# SCH_BlackRacer.net
KiCad netlist of a schematic drawn in EasyEDA
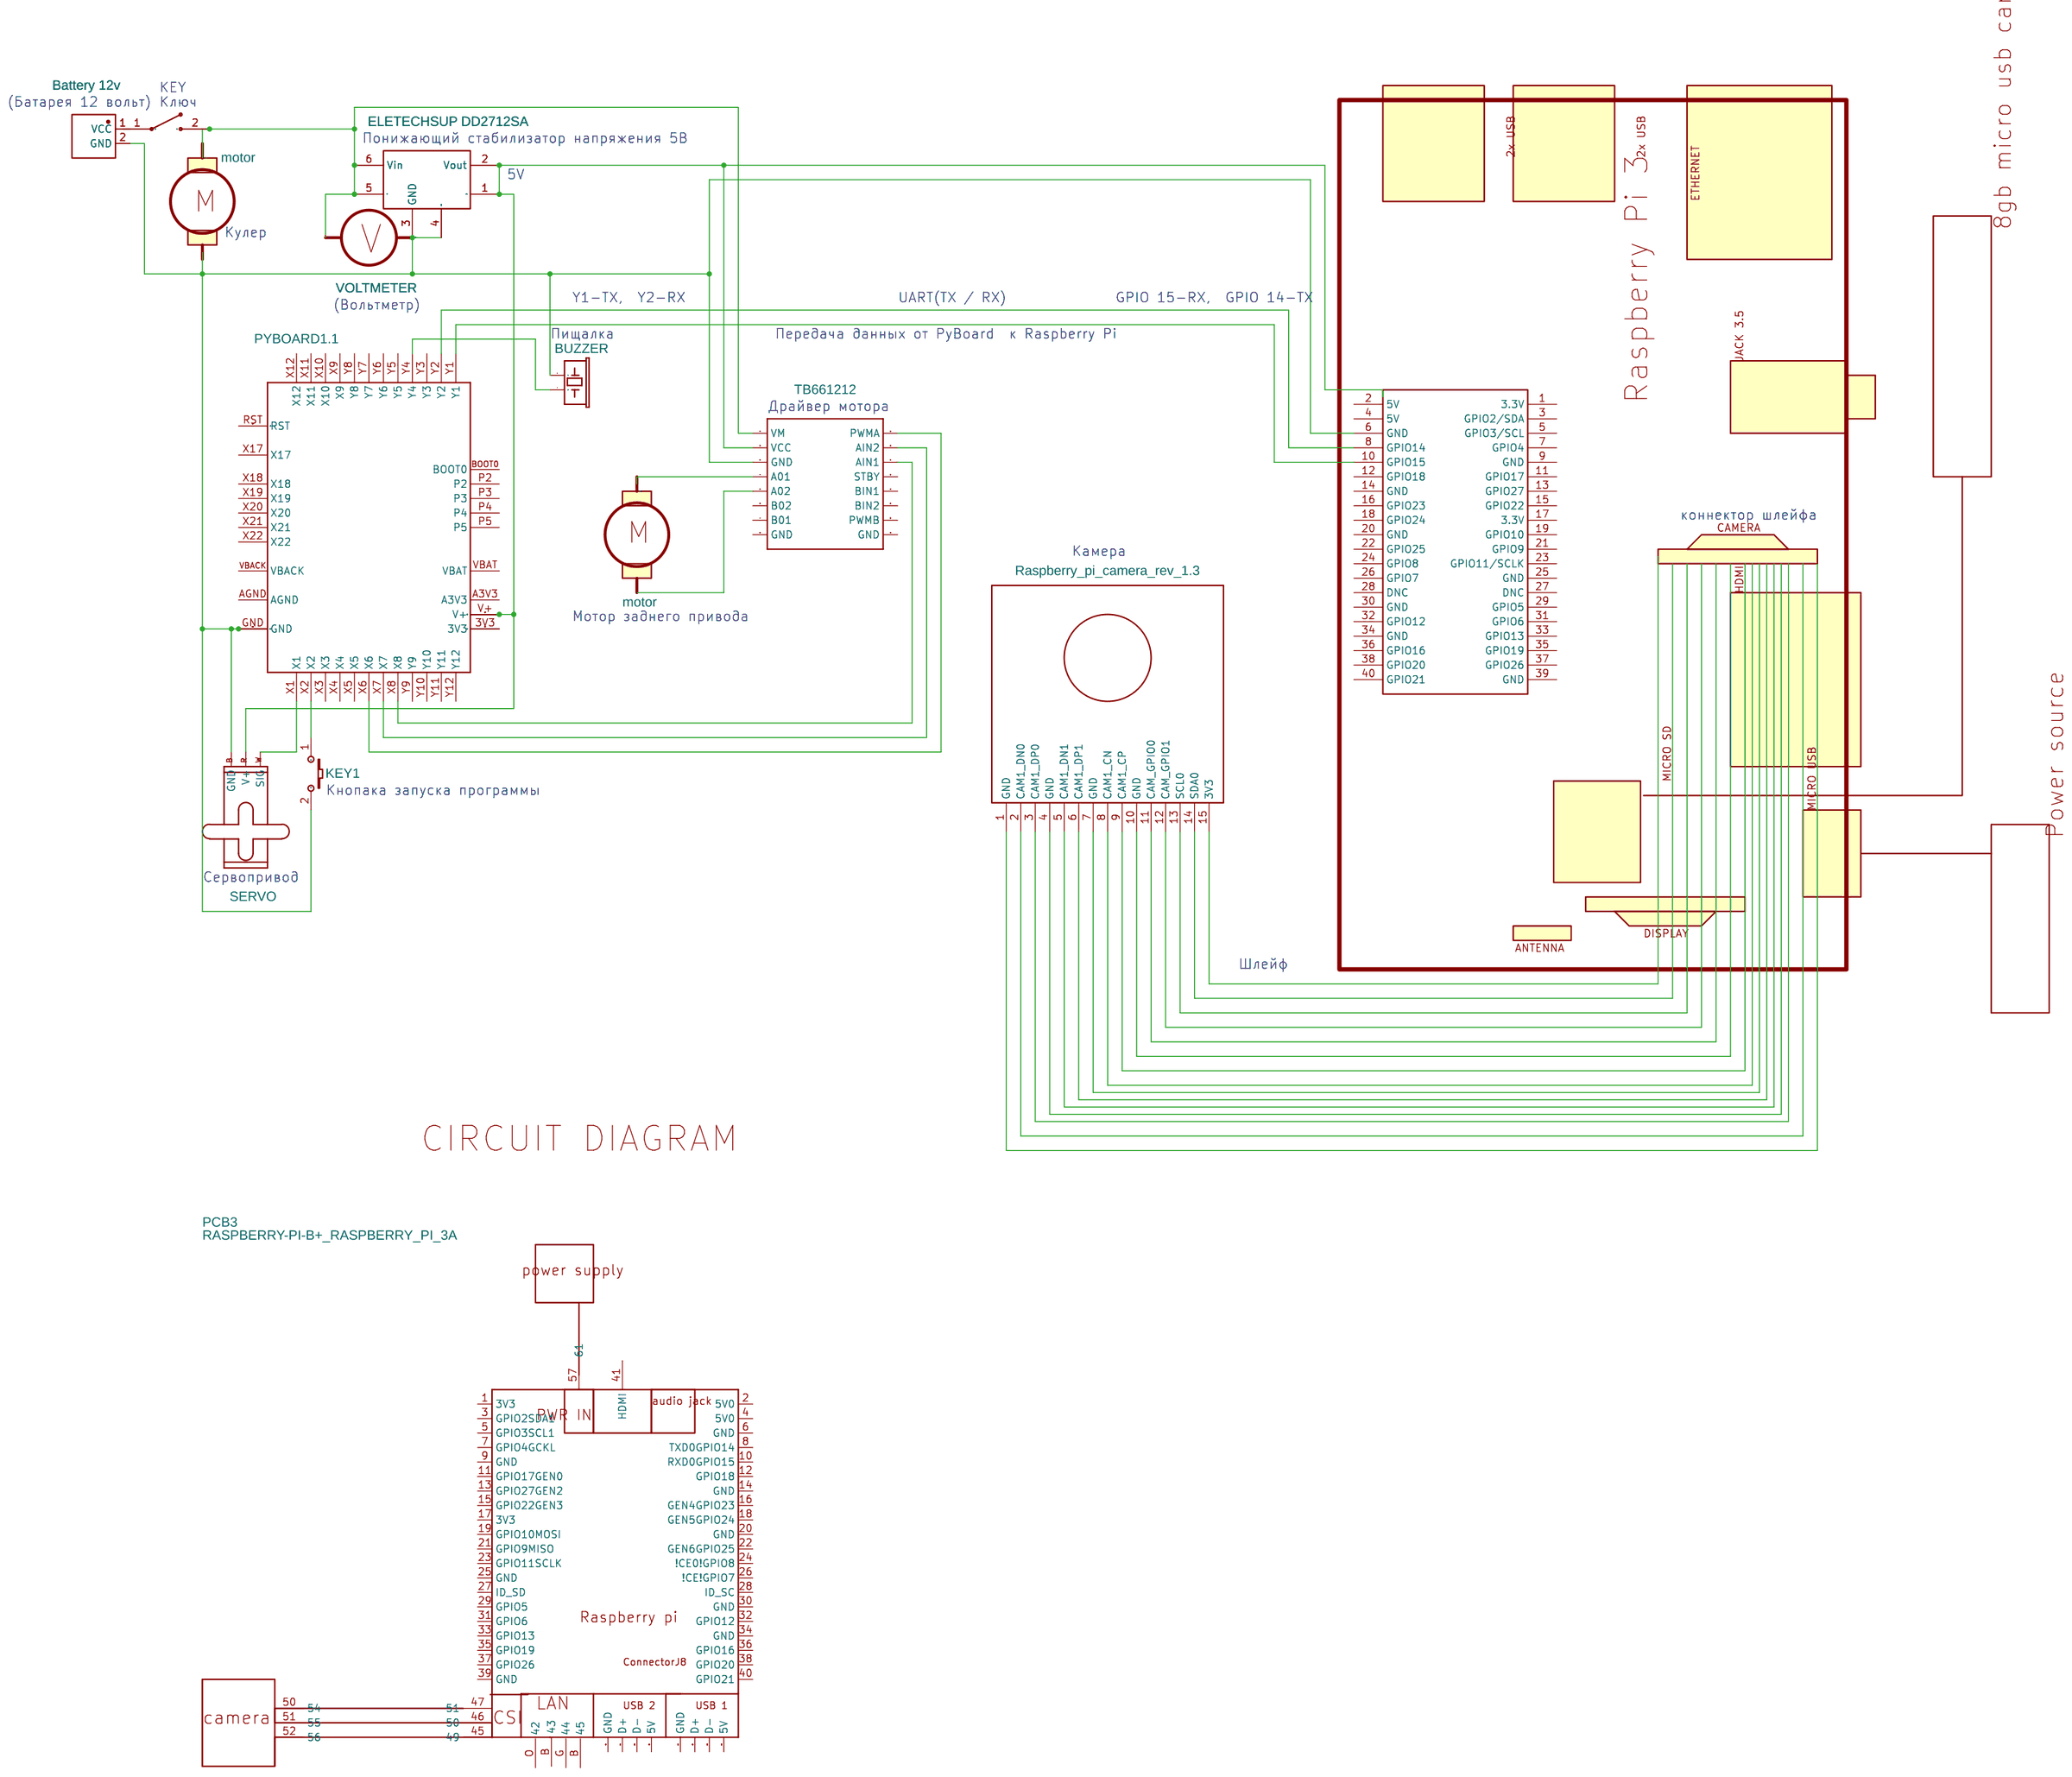
[diagram p0: schematic sheet]

(export (version "E")
  (design (tool "Eeschema 10.0.6"))
  (components
    (comp (ref "1") (value "PYBOARD1.1") (libsource (lib "") (part "PYBOARD1.1")))
    (comp (ref "KEY1")
      (value "K2-3.6×6.1_SMD")
      (fields
        (field (name "BOM_Manufacturer Part") "K2-1107ST-A4SW-06")
        (field (name "BOM_Supplier Part") "C118141")
      )
      (libsource (lib "") (part "K2-3.6×6.1_SMD"))
    )
    (comp (ref "M1") (value "SERVO") (libsource (lib "") (part "SERVO")))
    (comp (ref "M2") (value "motor") (libsource (lib "") (part "motor_1")))
    (comp (ref "M4") (value "motor") (libsource (lib "") (part "motor")))
    (comp (ref "P1") (value "VOLTMETER") (libsource (lib "") (part "VOLTMETER_XL")))
    (comp (ref "PCB3")
      (value "RASPBERRY-PI-B+_RASPBERRY_PI_3A")
      (libsource (lib "") (part "RASPBERRY-PI-B+_RASPBERRY_PI_3A"))
    )
    (comp (ref "SG1") (value "BUZZER") (libsource (lib "") (part "BUZZER")))
    (comp (ref "U1") (value "ELETECHSUP DD2712SA") (libsource (lib "") (part "DD2712SA")))
    (comp (ref "U2")
      (value "Raspberry Pi")
      (fields
        (field (name "BOM_Manufacturer Part") "RASPBERRY PI 3 Model B")
        (field (name "BOM_Supplier Part") "Raspberry Pi 3-B")
      )
      (libsource (lib "") (part "Raspberry Pi"))
    )
    (comp (ref "U4") (value "Battery 12v") (libsource (lib "") (part "Battery")))
    (comp (ref "U5")
      (value "Raspberry_pi_camera_rev_1.3")
      (libsource (lib "") (part "Raspberry_pi_camera_rev_1.3"))
    )
    (comp (ref "U7")
      (value "Botton")
      (fields (field (name "BOM_Manufacturer Part") "2A080") (field (name "BOM_Supplier Part") "12131"))
      (libsource (lib "") (part "Botton"))
    )
    (comp (ref "U9") (value "TB661212") (libsource (lib "") (part "TB661212")))
  )
  (nets
    (net (code "1") (name "Net-(1-3V3-Pad3V3-1)") (class "Default")
      (node (ref "1") (pin "3V3") (pinfunction "3V3_3V3") (pintype "bidirectional"))
      (node (ref "1") (pin "3V3-1") (pinfunction "3V3_3V3-1") (pintype "bidirectional"))
    )
    (net (code "2") (name "Net-(1-PadRST)") (class "Default")
      (node (ref "1") (pin "RST") (pinfunction "RST_RST") (pintype "bidirectional"))
      (node (ref "1") (pin "RST1") (pinfunction "RST_RST1") (pintype "bidirectional"))
    )
    (net (code "3") (name "Net-(1-PadX2)") (class "Default")
      (node (ref "1") (pin "X2") (pinfunction "X2_X2") (pintype "bidirectional"))
      (node (ref "KEY1") (pin "1") (pinfunction "1_1") (pintype "unspecified"))
    )
    (net (code "4") (name "Net-(M1-GND)") (class "Default")
      (node (ref "1") (pin "GND") (pinfunction "GND_GND") (pintype "bidirectional"))
      (node (ref "1") (pin "GND0") (pinfunction "GND_GND0") (pintype "bidirectional"))
      (node (ref "1") (pin "GND1") (pinfunction "GND_GND1") (pintype "bidirectional"))
      (node (ref "1") (pin "GND2") (pinfunction "GND_GND2") (pintype "bidirectional"))
      (node (ref "1") (pin "GND3") (pinfunction "GND_GND3") (pintype "bidirectional"))
      (node (ref "1") (pin "GND4") (pinfunction "GND_GND4") (pintype "bidirectional"))
      (node (ref "1") (pin "GND5") (pinfunction "GND_GND5") (pintype "bidirectional"))
      (node (ref "1") (pin "GND6") (pinfunction "GND_GND6") (pintype "bidirectional"))
      (node (ref "KEY1") (pin "2") (pinfunction "2_2") (pintype "unspecified"))
      (node (ref "M1") (pin "3") (pinfunction "GND_3") (pintype "bidirectional"))
      (node (ref "P1") (pin "2") (pinfunction "B_2") (pintype "unspecified"))
      (node (ref "SG1") (pin "+") (pinfunction "1_+") (pintype "unspecified"))
      (node (ref "U1") (pin "3") (pinfunction "GND_3") (pintype "unspecified"))
      (node (ref "U1") (pin "4") (pinfunction "GND_4") (pintype "unspecified"))
      (node (ref "U2") (pin "6") (pinfunction "GND_6") (pintype "unspecified"))
      (node (ref "U4") (pin "2") (pinfunction "GND_2") (pintype "unspecified"))
      (node (ref "U9") (pin "GND") (pinfunction "GND_GND") (pintype "passive"))
    )
    (net (code "5") (name "Net-(M1-SIG)") (class "Default")
      (node (ref "1") (pin "X1") (pinfunction "X1_X1") (pintype "bidirectional"))
      (node (ref "M1") (pin "1") (pinfunction "SIG_1") (pintype "bidirectional"))
    )
    (net (code "6") (name "Net-(M1-V+)") (class "Default")
      (node (ref "1") (pin "V+") (pinfunction "V+_V+") (pintype "bidirectional"))
      (node (ref "1") (pin "V+1") (pinfunction "V+_V+1") (pintype "bidirectional"))
      (node (ref "1") (pin "V+2") (pinfunction "V+_V+2") (pintype "bidirectional"))
      (node (ref "1") (pin "V+3") (pinfunction "V+_V+3") (pintype "bidirectional"))
      (node (ref "1") (pin "V+4") (pinfunction "V+_V+4") (pintype "bidirectional"))
      (node (ref "1") (pin "V+5") (pinfunction "V+_V+5") (pintype "bidirectional"))
      (node (ref "1") (pin "V+6") (pinfunction "V+_V+6") (pintype "bidirectional"))
      (node (ref "M1") (pin "2") (pinfunction "V+_2") (pintype "bidirectional"))
      (node (ref "U1") (pin "1") (pinfunction "Vout_1") (pintype "unspecified"))
      (node (ref "U1") (pin "2") (pinfunction "Vout_2") (pintype "unspecified"))
      (node (ref "U9") (pin "VCC") (pinfunction "VCC_VCC") (pintype "passive"))
    )
    (net (code "7") (name "Net-(P1-A)") (class "Default")
      (node (ref "M2") (pin "2") (pinfunction "2_2") (pintype "unspecified"))
      (node (ref "P1") (pin "1") (pinfunction "A_1") (pintype "unspecified"))
      (node (ref "U1") (pin "5") (pinfunction "Vin_5") (pintype "unspecified"))
      (node (ref "U1") (pin "6") (pinfunction "Vin_6") (pintype "unspecified"))
      (node (ref "U7") (pin "2") (pinfunction "1_2") (pintype "unspecified"))
      (node (ref "U9") (pin "VM") (pinfunction "VM_VM") (pintype "passive"))
    )
    (net (code "8") (name "Net-(SG1-2)") (class "Default")
      (node (ref "1") (pin "Y4") (pinfunction "Y4_Y4") (pintype "bidirectional"))
      (node (ref "SG1") (pin "-") (pinfunction "2_-") (pintype "unspecified"))
    )
    (net (code "9") (name "Net-(U2-GPIO14)") (class "Default")
      (node (ref "1") (pin "Y2") (pinfunction "Y2_Y2") (pintype "bidirectional"))
      (node (ref "U2") (pin "8") (pinfunction "GPIO14_8") (pintype "bidirectional"))
    )
    (net (code "10") (name "Net-(U2-GPIO15)") (class "Default")
      (node (ref "1") (pin "Y1") (pinfunction "Y1_Y1") (pintype "bidirectional"))
      (node (ref "U2") (pin "10") (pinfunction "GPIO15_10") (pintype "bidirectional"))
    )
    (net (code "11") (name "Net-(U9-AIN1)") (class "Default")
      (node (ref "1") (pin "X8") (pinfunction "X8_X8") (pintype "bidirectional"))
      (node (ref "U9") (pin "14") (pinfunction "AIN1_14") (pintype "unspecified"))
    )
    (net (code "12") (name "Net-(U9-AIN2)") (class "Default")
      (node (ref "1") (pin "X7") (pinfunction "X7_X7") (pintype "bidirectional"))
      (node (ref "U9") (pin "15") (pinfunction "AIN2_15") (pintype "unspecified"))
    )
    (net (code "13") (name "Net-(U9-PWMA)") (class "Default")
      (node (ref "1") (pin "X6") (pinfunction "X6_X6") (pintype "bidirectional"))
      (node (ref "U9") (pin "16") (pinfunction "PWMA_16") (pintype "unspecified"))
    )
    (net (code "14") (name "unconnected-(1-PadA3V3)") (class "Default")
      (node (ref "1") (pin "A3V3") (pinfunction "A3V3_A3V3") (pintype "bidirectional"))
    )
    (net (code "15") (name "unconnected-(1-PadAGND)") (class "Default")
      (node (ref "1") (pin "AGND") (pinfunction "AGND_AGND") (pintype "bidirectional"))
    )
    (net (code "16") (name "unconnected-(1-PadBOOT0)") (class "Default")
      (node (ref "1") (pin "BOOT0") (pinfunction "BOOT0_BOOT0") (pintype "bidirectional"))
    )
    (net (code "17") (name "unconnected-(1-PadP2)") (class "Default")
      (node (ref "1") (pin "P2") (pinfunction "P2_P2") (pintype "bidirectional"))
    )
    (net (code "18") (name "unconnected-(1-PadP3)") (class "Default")
      (node (ref "1") (pin "P3") (pinfunction "P3_P3") (pintype "bidirectional"))
    )
    (net (code "19") (name "unconnected-(1-PadP4)") (class "Default")
      (node (ref "1") (pin "P4") (pinfunction "P4_P4") (pintype "bidirectional"))
    )
    (net (code "20") (name "unconnected-(1-PadP5)") (class "Default")
      (node (ref "1") (pin "P5") (pinfunction "P5_P5") (pintype "bidirectional"))
    )
    (net (code "21") (name "unconnected-(1-PadVBACK)") (class "Default")
      (node (ref "1") (pin "VBACK") (pinfunction "VBACK_VBACK") (pintype "bidirectional"))
    )
    (net (code "22") (name "unconnected-(1-PadVBAT)") (class "Default")
      (node (ref "1") (pin "VBAT") (pinfunction "VBAT_VBAT") (pintype "bidirectional"))
    )
    (net (code "23") (name "unconnected-(1-PadX3)") (class "Default")
      (node (ref "1") (pin "X3") (pinfunction "X3_X3") (pintype "bidirectional"))
    )
    (net (code "24") (name "unconnected-(1-PadX4)") (class "Default")
      (node (ref "1") (pin "X4") (pinfunction "X4_X4") (pintype "bidirectional"))
    )
    (net (code "25") (name "unconnected-(1-PadX5)") (class "Default")
      (node (ref "1") (pin "X5") (pinfunction "X5_X5") (pintype "bidirectional"))
    )
    (net (code "26") (name "unconnected-(1-PadX9)") (class "Default")
      (node (ref "1") (pin "X9") (pinfunction "X9_X9") (pintype "bidirectional"))
    )
    (net (code "27") (name "unconnected-(1-PadX10)") (class "Default")
      (node (ref "1") (pin "X10") (pinfunction "X10_X10") (pintype "bidirectional"))
    )
    (net (code "28") (name "unconnected-(1-PadX11)") (class "Default")
      (node (ref "1") (pin "X11") (pinfunction "X11_X11") (pintype "bidirectional"))
    )
    (net (code "29") (name "unconnected-(1-PadX12)") (class "Default")
      (node (ref "1") (pin "X12") (pinfunction "X12_X12") (pintype "bidirectional"))
    )
    (net (code "30") (name "unconnected-(1-PadX17)") (class "Default")
      (node (ref "1") (pin "X17") (pinfunction "X17_X17") (pintype "bidirectional"))
    )
    (net (code "31") (name "unconnected-(1-PadX18)") (class "Default")
      (node (ref "1") (pin "X18") (pinfunction "X18_X18") (pintype "bidirectional"))
    )
    (net (code "32") (name "unconnected-(1-PadX19)") (class "Default")
      (node (ref "1") (pin "X19") (pinfunction "X19_X19") (pintype "bidirectional"))
    )
    (net (code "33") (name "unconnected-(1-PadX20)") (class "Default")
      (node (ref "1") (pin "X20") (pinfunction "X20_X20") (pintype "bidirectional"))
    )
    (net (code "34") (name "unconnected-(1-PadX21)") (class "Default")
      (node (ref "1") (pin "X21") (pinfunction "X21_X21") (pintype "bidirectional"))
    )
    (net (code "35") (name "unconnected-(1-PadX22)") (class "Default")
      (node (ref "1") (pin "X22") (pinfunction "X22_X22") (pintype "bidirectional"))
    )
    (net (code "36") (name "unconnected-(1-PadY3)") (class "Default")
      (node (ref "1") (pin "Y3") (pinfunction "Y3_Y3") (pintype "bidirectional"))
    )
    (net (code "37") (name "unconnected-(1-PadY5)") (class "Default")
      (node (ref "1") (pin "Y5") (pinfunction "Y5_Y5") (pintype "bidirectional"))
    )
    (net (code "38") (name "unconnected-(1-PadY6)") (class "Default")
      (node (ref "1") (pin "Y6") (pinfunction "Y6_Y6") (pintype "bidirectional"))
    )
    (net (code "39") (name "unconnected-(1-PadY7)") (class "Default")
      (node (ref "1") (pin "Y7") (pinfunction "Y7_Y7") (pintype "bidirectional"))
    )
    (net (code "40") (name "unconnected-(1-PadY8)") (class "Default")
      (node (ref "1") (pin "Y8") (pinfunction "Y8_Y8") (pintype "bidirectional"))
    )
    (net (code "41") (name "unconnected-(1-PadY9)") (class "Default")
      (node (ref "1") (pin "Y9") (pinfunction "Y9_Y9") (pintype "bidirectional"))
    )
    (net (code "42") (name "unconnected-(1-PadY10)") (class "Default")
      (node (ref "1") (pin "Y10") (pinfunction "Y10_Y10") (pintype "bidirectional"))
    )
    (net (code "43") (name "unconnected-(1-PadY11)") (class "Default")
      (node (ref "1") (pin "Y11") (pinfunction "Y11_Y11") (pintype "bidirectional"))
    )
    (net (code "44") (name "unconnected-(1-PadY12)") (class "Default")
      (node (ref "1") (pin "Y12") (pinfunction "Y12_Y12") (pintype "bidirectional"))
    )
    (net (code "45") (name "unconnected-(M4-Pad2)") (class "Default")
      (node (ref "M4") (pin "2") (pinfunction "2_2") (pintype "unspecified"))
    )
    (net (code "46") (name "unconnected-(PCB3-!CE!GPIO7-Pad26)") (class "Default")
      (node (ref "PCB3") (pin "26") (pinfunction "!CE!GPIO7_26") (pintype "unspecified"))
    )
    (net (code "47") (name "unconnected-(PCB3-!CE0!GPIO8-Pad24)") (class "Default")
      (node (ref "PCB3") (pin "24") (pinfunction "!CE0!GPIO8_24") (pintype "unspecified"))
    )
    (net (code "48") (name "unconnected-(PCB3-3V3-Pad1)") (class "Default")
      (node (ref "PCB3") (pin "1") (pinfunction "3V3_1") (pintype "unspecified"))
    )
    (net (code "49") (name "unconnected-(PCB3-3V3-Pad17)") (class "Default")
      (node (ref "PCB3") (pin "17") (pinfunction "3V3_17") (pintype "unspecified"))
    )
    (net (code "50") (name "unconnected-(PCB3-5V-PadPE_BR)") (class "Default")
      (node (ref "PCB3") (pin "PE_BR") (pinfunction "5V_PE_BR") (pintype "unspecified"))
    )
    (net (code "51") (name "unconnected-(PCB3-5V-PadPE_BR)_1") (class "Default")
      (node (ref "PCB3") (pin "PE_BR") (pinfunction "5V_PE_BR") (pintype "unspecified"))
    )
    (net (code "52") (name "unconnected-(PCB3-5V0-Pad2)") (class "Default")
      (node (ref "PCB3") (pin "2") (pinfunction "5V0_2") (pintype "unspecified"))
    )
    (net (code "53") (name "unconnected-(PCB3-5V0-Pad4)") (class "Default")
      (node (ref "PCB3") (pin "4") (pinfunction "5V0_4") (pintype "unspecified"))
    )
    (net (code "54") (name "unconnected-(PCB3-42-PadO)") (class "Default")
      (node (ref "PCB3") (pin "O") (pinfunction "42_O") (pintype "unspecified"))
    )
    (net (code "55") (name "unconnected-(PCB3-43-PadB)") (class "Default")
      (node (ref "PCB3") (pin "B") (pinfunction "43_B") (pintype "unspecified"))
    )
    (net (code "56") (name "unconnected-(PCB3-44-PadG)") (class "Default")
      (node (ref "PCB3") (pin "G") (pinfunction "44_G") (pintype "unspecified"))
    )
    (net (code "57") (name "unconnected-(PCB3-45-PadB)") (class "Default")
      (node (ref "PCB3") (pin "B") (pinfunction "45_B") (pintype "unspecified"))
    )
    (net (code "58") (name "unconnected-(PCB3-49-Pad45)") (class "Default")
      (node (ref "PCB3") (pin "45") (pinfunction "49_45") (pintype "unspecified"))
    )
    (net (code "59") (name "unconnected-(PCB3-50-Pad46)") (class "Default")
      (node (ref "PCB3") (pin "46") (pinfunction "50_46") (pintype "unspecified"))
    )
    (net (code "60") (name "unconnected-(PCB3-51-Pad47)") (class "Default")
      (node (ref "PCB3") (pin "47") (pinfunction "51_47") (pintype "unspecified"))
    )
    (net (code "61") (name "unconnected-(PCB3-54-Pad50)") (class "Default")
      (node (ref "PCB3") (pin "50") (pinfunction "54_50") (pintype "unspecified"))
    )
    (net (code "62") (name "unconnected-(PCB3-55-Pad51)") (class "Default")
      (node (ref "PCB3") (pin "51") (pinfunction "55_51") (pintype "unspecified"))
    )
    (net (code "63") (name "unconnected-(PCB3-56-Pad52)") (class "Default")
      (node (ref "PCB3") (pin "52") (pinfunction "56_52") (pintype "unspecified"))
    )
    (net (code "64") (name "unconnected-(PCB3-61-Pad57)") (class "Default")
      (node (ref "PCB3") (pin "57") (pinfunction "61_57") (pintype "unspecified"))
    )
    (net (code "65") (name "unconnected-(PCB3-D+-PadPE_BR)") (class "Default")
      (node (ref "PCB3") (pin "PE_BR") (pinfunction "D+_PE_BR") (pintype "unspecified"))
    )
    (net (code "66") (name "unconnected-(PCB3-D+-PadPE_BR)_1") (class "Default")
      (node (ref "PCB3") (pin "PE_BR") (pinfunction "D+_PE_BR") (pintype "unspecified"))
    )
    (net (code "67") (name "unconnected-(PCB3-D--PadPE_BR)") (class "Default")
      (node (ref "PCB3") (pin "PE_BR") (pinfunction "D-_PE_BR") (pintype "unspecified"))
    )
    (net (code "68") (name "unconnected-(PCB3-D--PadPE_BR)_1") (class "Default")
      (node (ref "PCB3") (pin "PE_BR") (pinfunction "D-_PE_BR") (pintype "unspecified"))
    )
    (net (code "69") (name "unconnected-(PCB3-GEN4GPIO23-Pad16)") (class "Default")
      (node (ref "PCB3") (pin "16") (pinfunction "GEN4GPIO23_16") (pintype "unspecified"))
    )
    (net (code "70") (name "unconnected-(PCB3-GEN5GPIO24-Pad18)") (class "Default")
      (node (ref "PCB3") (pin "18") (pinfunction "GEN5GPIO24_18") (pintype "unspecified"))
    )
    (net (code "71") (name "unconnected-(PCB3-GEN6GPIO25-Pad22)") (class "Default")
      (node (ref "PCB3") (pin "22") (pinfunction "GEN6GPIO25_22") (pintype "unspecified"))
    )
    (net (code "72") (name "unconnected-(PCB3-GND-Pad6)") (class "Default")
      (node (ref "PCB3") (pin "6") (pinfunction "GND_6") (pintype "unspecified"))
    )
    (net (code "73") (name "unconnected-(PCB3-GND-Pad9)") (class "Default")
      (node (ref "PCB3") (pin "9") (pinfunction "GND_9") (pintype "unspecified"))
    )
    (net (code "74") (name "unconnected-(PCB3-GND-Pad14)") (class "Default")
      (node (ref "PCB3") (pin "14") (pinfunction "GND_14") (pintype "unspecified"))
    )
    (net (code "75") (name "unconnected-(PCB3-GND-Pad20)") (class "Default")
      (node (ref "PCB3") (pin "20") (pinfunction "GND_20") (pintype "unspecified"))
    )
    (net (code "76") (name "unconnected-(PCB3-GND-Pad25)") (class "Default")
      (node (ref "PCB3") (pin "25") (pinfunction "GND_25") (pintype "unspecified"))
    )
    (net (code "77") (name "unconnected-(PCB3-GND-Pad30)") (class "Default")
      (node (ref "PCB3") (pin "30") (pinfunction "GND_30") (pintype "unspecified"))
    )
    (net (code "78") (name "unconnected-(PCB3-GND-Pad34)") (class "Default")
      (node (ref "PCB3") (pin "34") (pinfunction "GND_34") (pintype "unspecified"))
    )
    (net (code "79") (name "unconnected-(PCB3-GND-Pad39)") (class "Default")
      (node (ref "PCB3") (pin "39") (pinfunction "GND_39") (pintype "unspecified"))
    )
    (net (code "80") (name "unconnected-(PCB3-GND-PadPE_BR)") (class "Default")
      (node (ref "PCB3") (pin "PE_BR") (pinfunction "GND_PE_BR") (pintype "unspecified"))
    )
    (net (code "81") (name "unconnected-(PCB3-GND-PadPE_BR)_1") (class "Default")
      (node (ref "PCB3") (pin "PE_BR") (pinfunction "GND_PE_BR") (pintype "unspecified"))
    )
    (net (code "82") (name "unconnected-(PCB3-GPIO2SDA1-Pad3)") (class "Default")
      (node (ref "PCB3") (pin "3") (pinfunction "GPIO2SDA1_3") (pintype "unspecified"))
    )
    (net (code "83") (name "unconnected-(PCB3-GPIO3SCL1-Pad5)") (class "Default")
      (node (ref "PCB3") (pin "5") (pinfunction "GPIO3SCL1_5") (pintype "unspecified"))
    )
    (net (code "84") (name "unconnected-(PCB3-GPIO4GCKL-Pad7)") (class "Default")
      (node (ref "PCB3") (pin "7") (pinfunction "GPIO4GCKL_7") (pintype "unspecified"))
    )
    (net (code "85") (name "unconnected-(PCB3-GPIO5-Pad29)") (class "Default")
      (node (ref "PCB3") (pin "29") (pinfunction "GPIO5_29") (pintype "unspecified"))
    )
    (net (code "86") (name "unconnected-(PCB3-GPIO6-Pad31)") (class "Default")
      (node (ref "PCB3") (pin "31") (pinfunction "GPIO6_31") (pintype "unspecified"))
    )
    (net (code "87") (name "unconnected-(PCB3-GPIO9MISO-Pad21)") (class "Default")
      (node (ref "PCB3") (pin "21") (pinfunction "GPIO9MISO_21") (pintype "unspecified"))
    )
    (net (code "88") (name "unconnected-(PCB3-GPIO10MOSI-Pad19)") (class "Default")
      (node (ref "PCB3") (pin "19") (pinfunction "GPIO10MOSI_19") (pintype "unspecified"))
    )
    (net (code "89") (name "unconnected-(PCB3-GPIO11SCLK-Pad23)") (class "Default")
      (node (ref "PCB3") (pin "23") (pinfunction "GPIO11SCLK_23") (pintype "unspecified"))
    )
    (net (code "90") (name "unconnected-(PCB3-GPIO12-Pad32)") (class "Default")
      (node (ref "PCB3") (pin "32") (pinfunction "GPIO12_32") (pintype "unspecified"))
    )
    (net (code "91") (name "unconnected-(PCB3-GPIO13-Pad33)") (class "Default")
      (node (ref "PCB3") (pin "33") (pinfunction "GPIO13_33") (pintype "unspecified"))
    )
    (net (code "92") (name "unconnected-(PCB3-GPIO16-Pad36)") (class "Default")
      (node (ref "PCB3") (pin "36") (pinfunction "GPIO16_36") (pintype "unspecified"))
    )
    (net (code "93") (name "unconnected-(PCB3-GPIO17GEN0-Pad11)") (class "Default")
      (node (ref "PCB3") (pin "11") (pinfunction "GPIO17GEN0_11") (pintype "unspecified"))
    )
    (net (code "94") (name "unconnected-(PCB3-GPIO18-Pad12)") (class "Default")
      (node (ref "PCB3") (pin "12") (pinfunction "GPIO18_12") (pintype "unspecified"))
    )
    (net (code "95") (name "unconnected-(PCB3-GPIO19-Pad35)") (class "Default")
      (node (ref "PCB3") (pin "35") (pinfunction "GPIO19_35") (pintype "unspecified"))
    )
    (net (code "96") (name "unconnected-(PCB3-GPIO20-Pad38)") (class "Default")
      (node (ref "PCB3") (pin "38") (pinfunction "GPIO20_38") (pintype "unspecified"))
    )
    (net (code "97") (name "unconnected-(PCB3-GPIO21-Pad40)") (class "Default")
      (node (ref "PCB3") (pin "40") (pinfunction "GPIO21_40") (pintype "unspecified"))
    )
    (net (code "98") (name "unconnected-(PCB3-GPIO22GEN3-Pad15)") (class "Default")
      (node (ref "PCB3") (pin "15") (pinfunction "GPIO22GEN3_15") (pintype "unspecified"))
    )
    (net (code "99") (name "unconnected-(PCB3-GPIO26-Pad37)") (class "Default")
      (node (ref "PCB3") (pin "37") (pinfunction "GPIO26_37") (pintype "unspecified"))
    )
    (net (code "100") (name "unconnected-(PCB3-GPIO27GEN2-Pad13)") (class "Default")
      (node (ref "PCB3") (pin "13") (pinfunction "GPIO27GEN2_13") (pintype "unspecified"))
    )
    (net (code "101") (name "unconnected-(PCB3-HDMI-Pad41)") (class "Default")
      (node (ref "PCB3") (pin "41") (pinfunction "HDMI_41") (pintype "unspecified"))
    )
    (net (code "102") (name "unconnected-(PCB3-ID_SC-Pad28)") (class "Default")
      (node (ref "PCB3") (pin "28") (pinfunction "ID_SC_28") (pintype "unspecified"))
    )
    (net (code "103") (name "unconnected-(PCB3-ID_SD-Pad27)") (class "Default")
      (node (ref "PCB3") (pin "27") (pinfunction "ID_SD_27") (pintype "unspecified"))
    )
    (net (code "104") (name "unconnected-(PCB3-RXD0GPIO15-Pad10)") (class "Default")
      (node (ref "PCB3") (pin "10") (pinfunction "RXD0GPIO15_10") (pintype "unspecified"))
    )
    (net (code "105") (name "unconnected-(PCB3-TXD0GPIO14-Pad8)") (class "Default")
      (node (ref "PCB3") (pin "8") (pinfunction "TXD0GPIO14_8") (pintype "unspecified"))
    )
    (net (code "106") (name "unconnected-(U2-3.3V-Pad1)") (class "Default")
      (node (ref "U2") (pin "1") (pinfunction "3.3V_1") (pintype "passive"))
    )
    (net (code "107") (name "unconnected-(U2-3.3V-Pad17)") (class "Default")
      (node (ref "U2") (pin "17") (pinfunction "3.3V_17") (pintype "passive"))
    )
    (net (code "108") (name "unconnected-(U2-5V-Pad2)") (class "Default")
      (node (ref "U2") (pin "2") (pinfunction "5V_2") (pintype "passive"))
    )
    (net (code "109") (name "unconnected-(U2-5V-Pad4)") (class "Default")
      (node (ref "U2") (pin "4") (pinfunction "5V_4") (pintype "passive"))
    )
    (net (code "110") (name "unconnected-(U2-DNC-Pad27)") (class "Default")
      (node (ref "U2") (pin "27") (pinfunction "DNC_27") (pintype "unspecified"))
    )
    (net (code "111") (name "unconnected-(U2-DNC-Pad28)") (class "Default")
      (node (ref "U2") (pin "28") (pinfunction "DNC_28") (pintype "unspecified"))
    )
    (net (code "112") (name "unconnected-(U2-GND-Pad9)") (class "Default")
      (node (ref "U2") (pin "9") (pinfunction "GND_9") (pintype "unspecified"))
    )
    (net (code "113") (name "unconnected-(U2-GND-Pad14)") (class "Default")
      (node (ref "U2") (pin "14") (pinfunction "GND_14") (pintype "unspecified"))
    )
    (net (code "114") (name "unconnected-(U2-GND-Pad20)") (class "Default")
      (node (ref "U2") (pin "20") (pinfunction "GND_20") (pintype "unspecified"))
    )
    (net (code "115") (name "unconnected-(U2-GND-Pad25)") (class "Default")
      (node (ref "U2") (pin "25") (pinfunction "GND_25") (pintype "unspecified"))
    )
    (net (code "116") (name "unconnected-(U2-GND-Pad30)") (class "Default")
      (node (ref "U2") (pin "30") (pinfunction "GND_30") (pintype "unspecified"))
    )
    (net (code "117") (name "unconnected-(U2-GND-Pad34)") (class "Default")
      (node (ref "U2") (pin "34") (pinfunction "GND_34") (pintype "unspecified"))
    )
    (net (code "118") (name "unconnected-(U2-GND-Pad39)") (class "Default")
      (node (ref "U2") (pin "39") (pinfunction "GND_39") (pintype "unspecified"))
    )
    (net (code "119") (name "unconnected-(U2-GPIO2{slash}SDA-Pad3)") (class "Default")
      (node (ref "U2") (pin "3") (pinfunction "GPIO2/SDA_3") (pintype "bidirectional"))
    )
    (net (code "120") (name "unconnected-(U2-GPIO3{slash}SCL-Pad5)") (class "Default")
      (node (ref "U2") (pin "5") (pinfunction "GPIO3/SCL_5") (pintype "bidirectional"))
    )
    (net (code "121") (name "unconnected-(U2-GPIO4-Pad7)") (class "Default")
      (node (ref "U2") (pin "7") (pinfunction "GPIO4_7") (pintype "bidirectional"))
    )
    (net (code "122") (name "unconnected-(U2-GPIO5-Pad29)") (class "Default")
      (node (ref "U2") (pin "29") (pinfunction "GPIO5_29") (pintype "bidirectional"))
    )
    (net (code "123") (name "unconnected-(U2-GPIO6-Pad31)") (class "Default")
      (node (ref "U2") (pin "31") (pinfunction "GPIO6_31") (pintype "bidirectional"))
    )
    (net (code "124") (name "unconnected-(U2-GPIO7-Pad26)") (class "Default")
      (node (ref "U2") (pin "26") (pinfunction "GPIO7_26") (pintype "bidirectional"))
    )
    (net (code "125") (name "unconnected-(U2-GPIO8-Pad24)") (class "Default")
      (node (ref "U2") (pin "24") (pinfunction "GPIO8_24") (pintype "bidirectional"))
    )
    (net (code "126") (name "unconnected-(U2-GPIO9-Pad21)") (class "Default")
      (node (ref "U2") (pin "21") (pinfunction "GPIO9_21") (pintype "bidirectional"))
    )
    (net (code "127") (name "unconnected-(U2-GPIO10-Pad19)") (class "Default")
      (node (ref "U2") (pin "19") (pinfunction "GPIO10_19") (pintype "bidirectional"))
    )
    (net (code "128") (name "unconnected-(U2-GPIO11{slash}SCLK-Pad23)") (class "Default")
      (node (ref "U2") (pin "23") (pinfunction "GPIO11/SCLK_23") (pintype "bidirectional"))
    )
    (net (code "129") (name "unconnected-(U2-GPIO12-Pad32)") (class "Default")
      (node (ref "U2") (pin "32") (pinfunction "GPIO12_32") (pintype "bidirectional"))
    )
    (net (code "130") (name "unconnected-(U2-GPIO13-Pad33)") (class "Default")
      (node (ref "U2") (pin "33") (pinfunction "GPIO13_33") (pintype "bidirectional"))
    )
    (net (code "131") (name "unconnected-(U2-GPIO16-Pad36)") (class "Default")
      (node (ref "U2") (pin "36") (pinfunction "GPIO16_36") (pintype "bidirectional"))
    )
    (net (code "132") (name "unconnected-(U2-GPIO17-Pad11)") (class "Default")
      (node (ref "U2") (pin "11") (pinfunction "GPIO17_11") (pintype "bidirectional"))
    )
    (net (code "133") (name "unconnected-(U2-GPIO18-Pad12)") (class "Default")
      (node (ref "U2") (pin "12") (pinfunction "GPIO18_12") (pintype "bidirectional"))
    )
    (net (code "134") (name "unconnected-(U2-GPIO19-Pad35)") (class "Default")
      (node (ref "U2") (pin "35") (pinfunction "GPIO19_35") (pintype "bidirectional"))
    )
    (net (code "135") (name "unconnected-(U2-GPIO20-Pad38)") (class "Default")
      (node (ref "U2") (pin "38") (pinfunction "GPIO20_38") (pintype "bidirectional"))
    )
    (net (code "136") (name "unconnected-(U2-GPIO21-Pad40)") (class "Default")
      (node (ref "U2") (pin "40") (pinfunction "GPIO21_40") (pintype "bidirectional"))
    )
    (net (code "137") (name "unconnected-(U2-GPIO22-Pad15)") (class "Default")
      (node (ref "U2") (pin "15") (pinfunction "GPIO22_15") (pintype "bidirectional"))
    )
    (net (code "138") (name "unconnected-(U2-GPIO23-Pad16)") (class "Default")
      (node (ref "U2") (pin "16") (pinfunction "GPIO23_16") (pintype "bidirectional"))
    )
    (net (code "139") (name "unconnected-(U2-GPIO24-Pad18)") (class "Default")
      (node (ref "U2") (pin "18") (pinfunction "GPIO24_18") (pintype "bidirectional"))
    )
    (net (code "140") (name "unconnected-(U2-GPIO25-Pad22)") (class "Default")
      (node (ref "U2") (pin "22") (pinfunction "GPIO25_22") (pintype "bidirectional"))
    )
    (net (code "141") (name "unconnected-(U2-GPIO26-Pad37)") (class "Default")
      (node (ref "U2") (pin "37") (pinfunction "GPIO26_37") (pintype "bidirectional"))
    )
    (net (code "142") (name "unconnected-(U2-GPIO27-Pad13)") (class "Default")
      (node (ref "U2") (pin "13") (pinfunction "GPIO27_13") (pintype "bidirectional"))
    )
    (net (code "143") (name "unconnected-(U4-VCC-Pad1)") (class "Default")
      (node (ref "U4") (pin "1") (pinfunction "VCC_1") (pintype "unspecified"))
    )
    (net (code "144") (name "unconnected-(U5-3V3-Pad15)") (class "Default")
      (node (ref "U5") (pin "15") (pinfunction "3V3_15") (pintype "unspecified"))
    )
    (net (code "145") (name "unconnected-(U5-CAM1_CN-Pad8)") (class "Default")
      (node (ref "U5") (pin "8") (pinfunction "CAM1_CN_8") (pintype "unspecified"))
    )
    (net (code "146") (name "unconnected-(U5-CAM1_CP-Pad9)") (class "Default")
      (node (ref "U5") (pin "9") (pinfunction "CAM1_CP_9") (pintype "unspecified"))
    )
    (net (code "147") (name "unconnected-(U5-CAM1_DN0-Pad2)") (class "Default")
      (node (ref "U5") (pin "2") (pinfunction "CAM1_DN0_2") (pintype "unspecified"))
    )
    (net (code "148") (name "unconnected-(U5-CAM1_DN1-Pad5)") (class "Default")
      (node (ref "U5") (pin "5") (pinfunction "CAM1_DN1_5") (pintype "unspecified"))
    )
    (net (code "149") (name "unconnected-(U5-CAM1_DP0-Pad3)") (class "Default")
      (node (ref "U5") (pin "3") (pinfunction "CAM1_DP0_3") (pintype "unspecified"))
    )
    (net (code "150") (name "unconnected-(U5-CAM1_DP1-Pad6)") (class "Default")
      (node (ref "U5") (pin "6") (pinfunction "CAM1_DP1_6") (pintype "unspecified"))
    )
    (net (code "151") (name "unconnected-(U5-CAM_GPIO0-Pad11)") (class "Default")
      (node (ref "U5") (pin "11") (pinfunction "CAM_GPIO0_11") (pintype "unspecified"))
    )
    (net (code "152") (name "unconnected-(U5-CAM_GPIO1-Pad12)") (class "Default")
      (node (ref "U5") (pin "12") (pinfunction "CAM_GPIO1_12") (pintype "unspecified"))
    )
    (net (code "153") (name "unconnected-(U5-GND-Pad1)") (class "Default")
      (node (ref "U5") (pin "1") (pinfunction "GND_1") (pintype "unspecified"))
    )
    (net (code "154") (name "unconnected-(U5-GND-Pad4)") (class "Default")
      (node (ref "U5") (pin "4") (pinfunction "GND_4") (pintype "unspecified"))
    )
    (net (code "155") (name "unconnected-(U5-GND-Pad7)") (class "Default")
      (node (ref "U5") (pin "7") (pinfunction "GND_7") (pintype "unspecified"))
    )
    (net (code "156") (name "unconnected-(U5-GND-Pad10)") (class "Default")
      (node (ref "U5") (pin "10") (pinfunction "GND_10") (pintype "unspecified"))
    )
    (net (code "157") (name "unconnected-(U5-SCL0-Pad13)") (class "Default")
      (node (ref "U5") (pin "13") (pinfunction "SCL0_13") (pintype "unspecified"))
    )
    (net (code "158") (name "unconnected-(U5-SDA0-Pad14)") (class "Default")
      (node (ref "U5") (pin "14") (pinfunction "SDA0_14") (pintype "unspecified"))
    )
    (net (code "159") (name "unconnected-(U7-2-Pad1)") (class "Default")
      (node (ref "U7") (pin "1") (pinfunction "2_1") (pintype "unspecified"))
    )
    (net (code "160") (name "unconnected-(U9-A01-Pad4)") (class "Default")
      (node (ref "U9") (pin "4") (pinfunction "A01_4") (pintype "unspecified"))
    )
    (net (code "161") (name "unconnected-(U9-A02-Pad5)") (class "Default")
      (node (ref "U9") (pin "5") (pinfunction "A02_5") (pintype "unspecified"))
    )
    (net (code "162") (name "unconnected-(U9-B01-Pad7)") (class "Default")
      (node (ref "U9") (pin "7") (pinfunction "B01_7") (pintype "unspecified"))
    )
    (net (code "163") (name "unconnected-(U9-B02-Pad6)") (class "Default")
      (node (ref "U9") (pin "6") (pinfunction "B02_6") (pintype "unspecified"))
    )
    (net (code "164") (name "unconnected-(U9-BIN1-Pad12)") (class "Default")
      (node (ref "U9") (pin "12") (pinfunction "BIN1_12") (pintype "unspecified"))
    )
    (net (code "165") (name "unconnected-(U9-BIN2-Pad11)") (class "Default")
      (node (ref "U9") (pin "11") (pinfunction "BIN2_11") (pintype "unspecified"))
    )
    (net (code "166") (name "unconnected-(U9-GND-Pad8)") (class "Default")
      (node (ref "U9") (pin "8") (pinfunction "GND_8") (pintype "passive"))
    )
    (net (code "167") (name "unconnected-(U9-GND-Pad56)") (class "Default")
      (node (ref "U9") (pin "56") (pinfunction "GND_56") (pintype "passive"))
    )
    (net (code "168") (name "unconnected-(U9-PWMB-Pad10)") (class "Default")
      (node (ref "U9") (pin "10") (pinfunction "PWMB_10") (pintype "unspecified"))
    )
    (net (code "169") (name "unconnected-(U9-STBY-Pad13)") (class "Default")
      (node (ref "U9") (pin "13") (pinfunction "STBY_13") (pintype "unspecified"))
    )
  )
)
